# slave-16.net
KiCad netlist of a schematic drawn in EAGLE
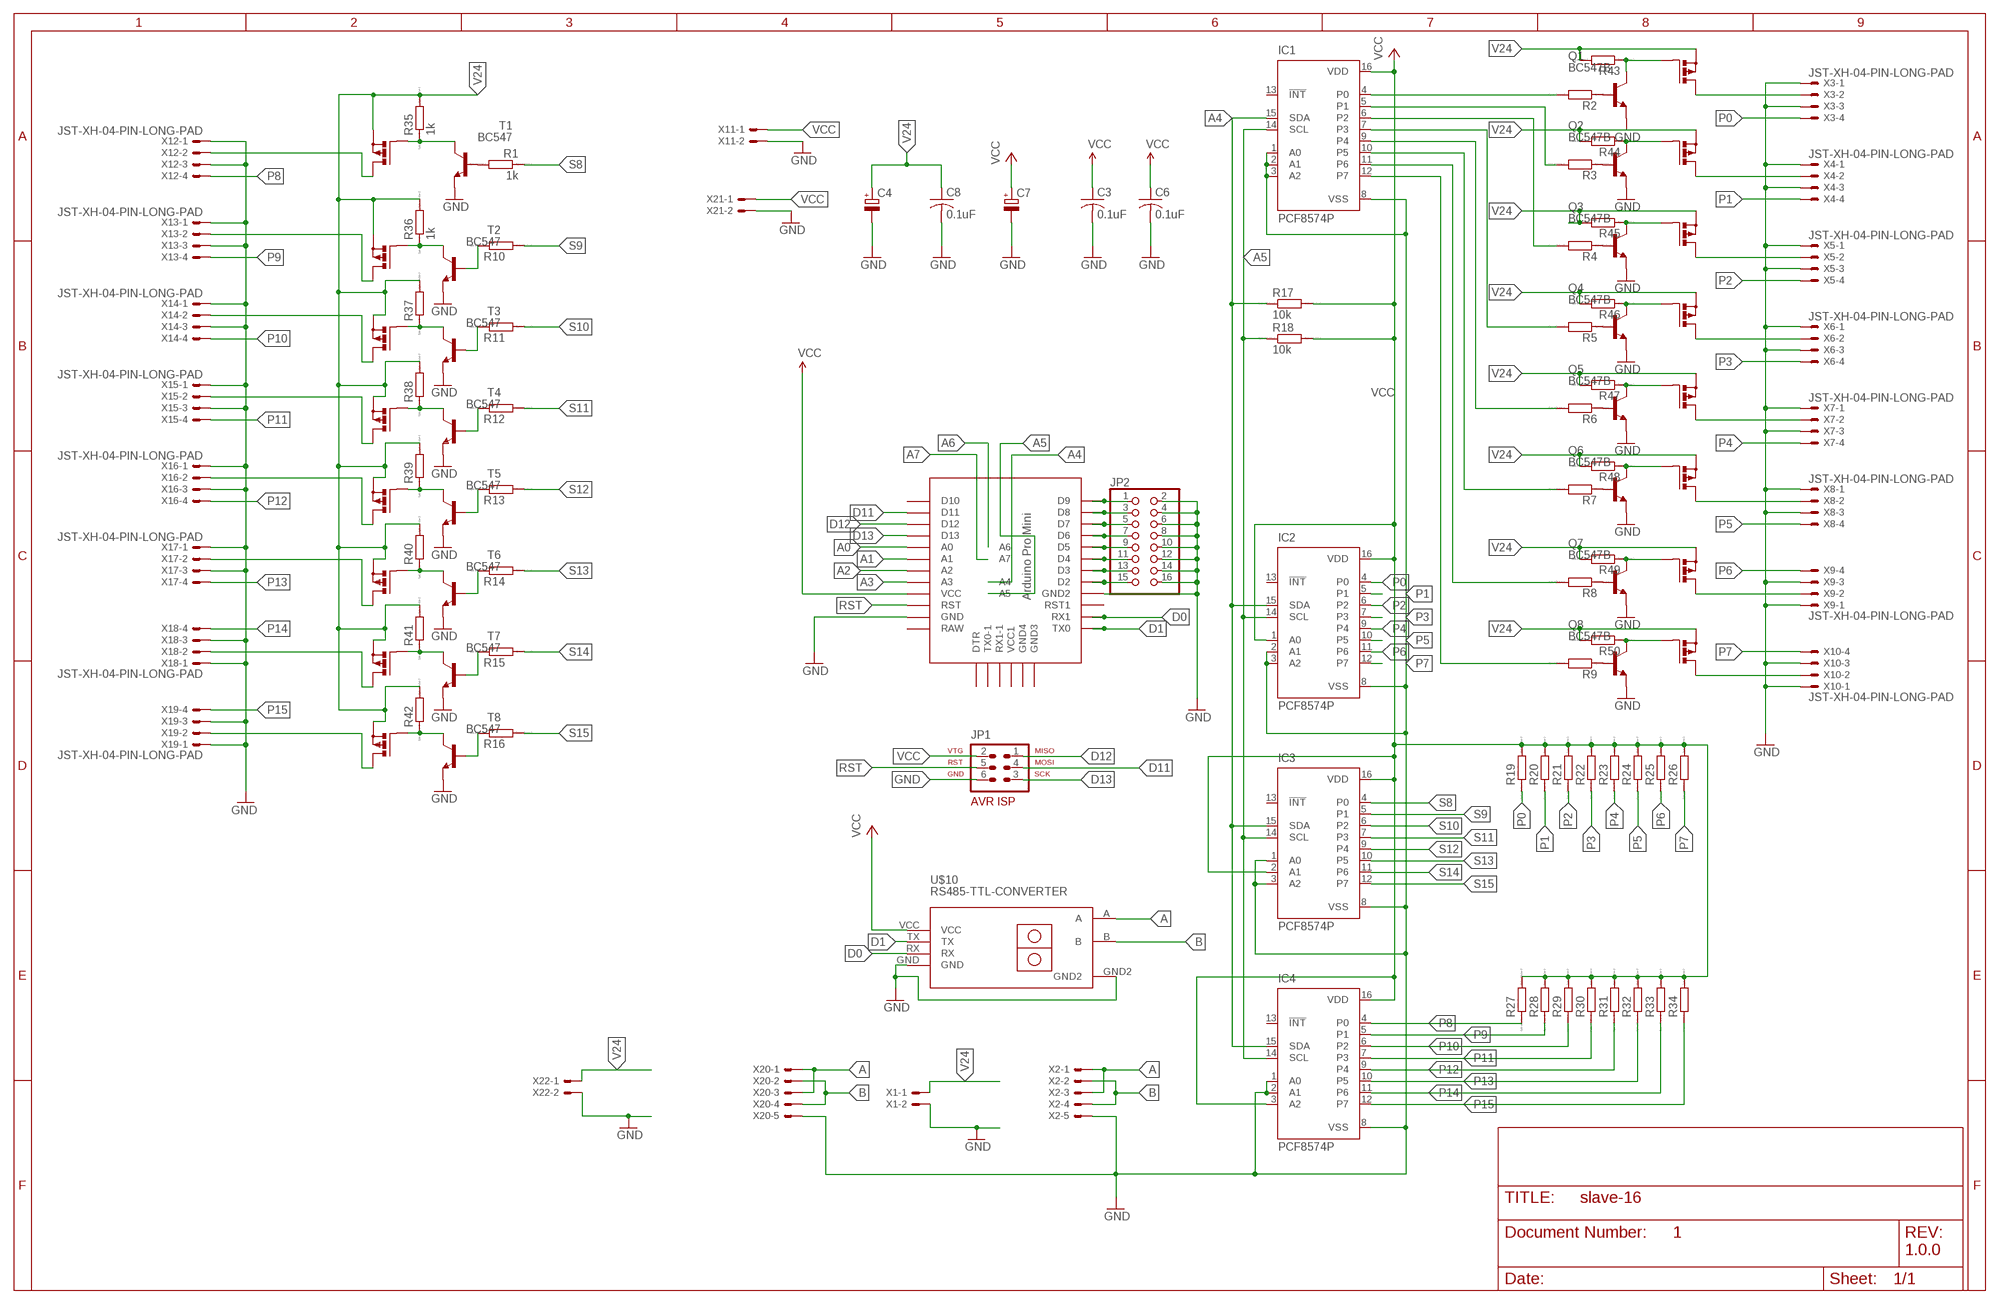
[diagram p0: schematic, sheet 1]

(export (version "E")
  (design (tool "Eeschema 10.0.6"))
  (components
    (comp (ref "C3")
      (value "0.1uF")
      (footprint "eagle-import:C0805")
      (libsource (lib "eagle-import") (part "C-USC0805"))
    )
    (comp (ref "C4")
      (value "CPOL-EUSANYO_SMD_C6")
      (footprint "eagle-import:SANYO-OSCON_SMD_C6")
      (libsource (lib "eagle-import") (part "CPOL-EUSANYO_SMD_C6"))
    )
    (comp (ref "C6")
      (value "0.1uF")
      (footprint "eagle-import:C0805")
      (libsource (lib "eagle-import") (part "C-USC0805"))
    )
    (comp (ref "C7")
      (value "CPOL-EUSANYO_SMD_C6")
      (footprint "eagle-import:SANYO-OSCON_SMD_C6")
      (libsource (lib "eagle-import") (part "CPOL-EUSANYO_SMD_C6"))
    )
    (comp (ref "C8")
      (value "0.1uF")
      (footprint "eagle-import:C0805")
      (libsource (lib "eagle-import") (part "C-USC0805"))
    )
    (comp (ref "IC1")
      (value "PCF8574P")
      (footprint "eagle-import:DIL16")
      (fields (field (name "MPN") "PCF8574PN"))
      (libsource (lib "eagle-import") (part "PCF8574P"))
    )
    (comp (ref "IC2")
      (value "PCF8574P")
      (footprint "eagle-import:DIL16")
      (fields (field (name "MPN") "PCF8574PN"))
      (libsource (lib "eagle-import") (part "PCF8574P"))
    )
    (comp (ref "IC3")
      (value "PCF8574P")
      (footprint "eagle-import:DIL16")
      (fields (field (name "MPN") "PCF8574PN"))
      (libsource (lib "eagle-import") (part "PCF8574P"))
    )
    (comp (ref "IC4")
      (value "PCF8574P")
      (footprint "eagle-import:DIL16")
      (fields (field (name "MPN") "PCF8574PN"))
      (libsource (lib "eagle-import") (part "PCF8574P"))
    )
    (comp (ref "JP1")
      (value "AVR-ISP-6")
      (footprint "eagle-import:AVR-ISP-6")
      (libsource (lib "eagle-import") (part "AVR-ISP-6"))
    )
    (comp (ref "JP2")
      (value "PINHD-2X8")
      (footprint "eagle-import:2X08")
      (libsource (lib "eagle-import") (part "PINHD-2X8"))
    )
    (comp (ref "Q1")
      (value "BC547B")
      (footprint "eagle-import:TO92")
      (libsource (lib "eagle-import") (part "BC547B"))
    )
    (comp (ref "Q2")
      (value "BC547B")
      (footprint "eagle-import:TO92")
      (libsource (lib "eagle-import") (part "BC547B"))
    )
    (comp (ref "Q3")
      (value "BC547B")
      (footprint "eagle-import:TO92")
      (libsource (lib "eagle-import") (part "BC547B"))
    )
    (comp (ref "Q4")
      (value "BC547B")
      (footprint "eagle-import:TO92")
      (libsource (lib "eagle-import") (part "BC547B"))
    )
    (comp (ref "Q5")
      (value "BC547B")
      (footprint "eagle-import:TO92")
      (libsource (lib "eagle-import") (part "BC547B"))
    )
    (comp (ref "Q6")
      (value "BC547B")
      (footprint "eagle-import:TO92")
      (libsource (lib "eagle-import") (part "BC547B"))
    )
    (comp (ref "Q7")
      (value "BC547B")
      (footprint "eagle-import:TO92")
      (libsource (lib "eagle-import") (part "BC547B"))
    )
    (comp (ref "Q8")
      (value "BC547B")
      (footprint "eagle-import:TO92")
      (libsource (lib "eagle-import") (part "BC547B"))
    )
    (comp (ref "R1")
      (value "1k")
      (footprint "eagle-import:R1206")
      (libsource (lib "eagle-import") (part "RR1206"))
    )
    (comp (ref "R2")
      (value "RR1206")
      (footprint "eagle-import:R1206")
      (libsource (lib "eagle-import") (part "RR1206"))
    )
    (comp (ref "R3")
      (value "RR1206")
      (footprint "eagle-import:R1206")
      (libsource (lib "eagle-import") (part "RR1206"))
    )
    (comp (ref "R4")
      (value "RR1206")
      (footprint "eagle-import:R1206")
      (libsource (lib "eagle-import") (part "RR1206"))
    )
    (comp (ref "R5")
      (value "RR1206")
      (footprint "eagle-import:R1206")
      (libsource (lib "eagle-import") (part "RR1206"))
    )
    (comp (ref "R6")
      (value "RR1206")
      (footprint "eagle-import:R1206")
      (libsource (lib "eagle-import") (part "RR1206"))
    )
    (comp (ref "R7")
      (value "RR1206")
      (footprint "eagle-import:R1206")
      (libsource (lib "eagle-import") (part "RR1206"))
    )
    (comp (ref "R8")
      (value "RR1206")
      (footprint "eagle-import:R1206")
      (libsource (lib "eagle-import") (part "RR1206"))
    )
    (comp (ref "R9")
      (value "RR1206")
      (footprint "eagle-import:R1206")
      (libsource (lib "eagle-import") (part "RR1206"))
    )
    (comp (ref "R10")
      (value "RR1206")
      (footprint "eagle-import:R1206")
      (libsource (lib "eagle-import") (part "RR1206"))
    )
    (comp (ref "R11")
      (value "RR1206")
      (footprint "eagle-import:R1206")
      (libsource (lib "eagle-import") (part "RR1206"))
    )
    (comp (ref "R12")
      (value "RR1206")
      (footprint "eagle-import:R1206")
      (libsource (lib "eagle-import") (part "RR1206"))
    )
    (comp (ref "R13")
      (value "RR1206")
      (footprint "eagle-import:R1206")
      (libsource (lib "eagle-import") (part "RR1206"))
    )
    (comp (ref "R14")
      (value "RR1206")
      (footprint "eagle-import:R1206")
      (libsource (lib "eagle-import") (part "RR1206"))
    )
    (comp (ref "R15")
      (value "RR1206")
      (footprint "eagle-import:R1206")
      (libsource (lib "eagle-import") (part "RR1206"))
    )
    (comp (ref "R16")
      (value "RR1206")
      (footprint "eagle-import:R1206")
      (libsource (lib "eagle-import") (part "RR1206"))
    )
    (comp (ref "R17")
      (value "10k")
      (footprint "eagle-import:R1206")
      (libsource (lib "eagle-import") (part "RR1206"))
    )
    (comp (ref "R18")
      (value "10k")
      (footprint "eagle-import:R1206")
      (libsource (lib "eagle-import") (part "RR1206"))
    )
    (comp (ref "R19")
      (value "RR1206")
      (footprint "eagle-import:R1206")
      (libsource (lib "eagle-import") (part "RR1206"))
    )
    (comp (ref "R20")
      (value "RR1206")
      (footprint "eagle-import:R1206")
      (libsource (lib "eagle-import") (part "RR1206"))
    )
    (comp (ref "R21")
      (value "RR1206")
      (footprint "eagle-import:R1206")
      (libsource (lib "eagle-import") (part "RR1206"))
    )
    (comp (ref "R22")
      (value "RR1206")
      (footprint "eagle-import:R1206")
      (libsource (lib "eagle-import") (part "RR1206"))
    )
    (comp (ref "R23")
      (value "RR1206")
      (footprint "eagle-import:R1206")
      (libsource (lib "eagle-import") (part "RR1206"))
    )
    (comp (ref "R24")
      (value "RR1206")
      (footprint "eagle-import:R1206")
      (libsource (lib "eagle-import") (part "RR1206"))
    )
    (comp (ref "R25")
      (value "RR1206")
      (footprint "eagle-import:R1206")
      (libsource (lib "eagle-import") (part "RR1206"))
    )
    (comp (ref "R26")
      (value "RR1206")
      (footprint "eagle-import:R1206")
      (libsource (lib "eagle-import") (part "RR1206"))
    )
    (comp (ref "R27")
      (value "RR1206")
      (footprint "eagle-import:R1206")
      (libsource (lib "eagle-import") (part "RR1206"))
    )
    (comp (ref "R28")
      (value "RR1206")
      (footprint "eagle-import:R1206")
      (libsource (lib "eagle-import") (part "RR1206"))
    )
    (comp (ref "R29")
      (value "RR1206")
      (footprint "eagle-import:R1206")
      (libsource (lib "eagle-import") (part "RR1206"))
    )
    (comp (ref "R30")
      (value "RR1206")
      (footprint "eagle-import:R1206")
      (libsource (lib "eagle-import") (part "RR1206"))
    )
    (comp (ref "R31")
      (value "RR1206")
      (footprint "eagle-import:R1206")
      (libsource (lib "eagle-import") (part "RR1206"))
    )
    (comp (ref "R32")
      (value "RR1206")
      (footprint "eagle-import:R1206")
      (libsource (lib "eagle-import") (part "RR1206"))
    )
    (comp (ref "R33")
      (value "RR1206")
      (footprint "eagle-import:R1206")
      (libsource (lib "eagle-import") (part "RR1206"))
    )
    (comp (ref "R34")
      (value "RR1206")
      (footprint "eagle-import:R1206")
      (libsource (lib "eagle-import") (part "RR1206"))
    )
    (comp (ref "R35")
      (value "1k")
      (footprint "eagle-import:R1206")
      (libsource (lib "eagle-import") (part "RR1206"))
    )
    (comp (ref "R36")
      (value "1k")
      (footprint "eagle-import:R1206")
      (libsource (lib "eagle-import") (part "RR1206"))
    )
    (comp (ref "R37")
      (value "RR1206")
      (footprint "eagle-import:R1206")
      (libsource (lib "eagle-import") (part "RR1206"))
    )
    (comp (ref "R38")
      (value "RR1206")
      (footprint "eagle-import:R1206")
      (libsource (lib "eagle-import") (part "RR1206"))
    )
    (comp (ref "R39")
      (value "RR1206")
      (footprint "eagle-import:R1206")
      (libsource (lib "eagle-import") (part "RR1206"))
    )
    (comp (ref "R40")
      (value "RR1206")
      (footprint "eagle-import:R1206")
      (libsource (lib "eagle-import") (part "RR1206"))
    )
    (comp (ref "R41")
      (value "RR1206")
      (footprint "eagle-import:R1206")
      (libsource (lib "eagle-import") (part "RR1206"))
    )
    (comp (ref "R42")
      (value "RR1206")
      (footprint "eagle-import:R1206")
      (libsource (lib "eagle-import") (part "RR1206"))
    )
    (comp (ref "R43")
      (value "RR1206")
      (footprint "eagle-import:R1206")
      (libsource (lib "eagle-import") (part "RR1206"))
    )
    (comp (ref "R44")
      (value "RR1206")
      (footprint "eagle-import:R1206")
      (libsource (lib "eagle-import") (part "RR1206"))
    )
    (comp (ref "R45")
      (value "RR1206")
      (footprint "eagle-import:R1206")
      (libsource (lib "eagle-import") (part "RR1206"))
    )
    (comp (ref "R46")
      (value "RR1206")
      (footprint "eagle-import:R1206")
      (libsource (lib "eagle-import") (part "RR1206"))
    )
    (comp (ref "R47")
      (value "RR1206")
      (footprint "eagle-import:R1206")
      (libsource (lib "eagle-import") (part "RR1206"))
    )
    (comp (ref "R48")
      (value "RR1206")
      (footprint "eagle-import:R1206")
      (libsource (lib "eagle-import") (part "RR1206"))
    )
    (comp (ref "R49")
      (value "RR1206")
      (footprint "eagle-import:R1206")
      (libsource (lib "eagle-import") (part "RR1206"))
    )
    (comp (ref "R50")
      (value "RR1206")
      (footprint "eagle-import:R1206")
      (libsource (lib "eagle-import") (part "RR1206"))
    )
    (comp (ref "T1")
      (value "BC547")
      (footprint "eagle-import:TO92")
      (libsource (lib "eagle-import") (part "transistor_402_BC547"))
    )
    (comp (ref "T2")
      (value "BC547")
      (footprint "eagle-import:TO92")
      (libsource (lib "eagle-import") (part "transistor_402_BC547"))
    )
    (comp (ref "T3")
      (value "BC547")
      (footprint "eagle-import:TO92")
      (libsource (lib "eagle-import") (part "transistor_402_BC547"))
    )
    (comp (ref "T4")
      (value "BC547")
      (footprint "eagle-import:TO92")
      (libsource (lib "eagle-import") (part "transistor_402_BC547"))
    )
    (comp (ref "T5")
      (value "BC547")
      (footprint "eagle-import:TO92")
      (libsource (lib "eagle-import") (part "transistor_402_BC547"))
    )
    (comp (ref "T6")
      (value "BC547")
      (footprint "eagle-import:TO92")
      (libsource (lib "eagle-import") (part "transistor_402_BC547"))
    )
    (comp (ref "T7")
      (value "BC547")
      (footprint "eagle-import:TO92")
      (libsource (lib "eagle-import") (part "transistor_402_BC547"))
    )
    (comp (ref "T8")
      (value "BC547")
      (footprint "eagle-import:TO92")
      (libsource (lib "eagle-import") (part "transistor_402_BC547"))
    )
    (comp (ref "U$1")
      (value "IRLML6402")
      (footprint "eagle-import:SOT-23")
      (libsource (lib "eagle-import") (part "IRLML6402"))
    )
    (comp (ref "U$2")
      (value "IRLML6402")
      (footprint "eagle-import:SOT-23")
      (libsource (lib "eagle-import") (part "IRLML6402"))
    )
    (comp (ref "U$3")
      (value "IRLML6402")
      (footprint "eagle-import:SOT-23")
      (libsource (lib "eagle-import") (part "IRLML6402"))
    )
    (comp (ref "U$4")
      (value "IRLML6402")
      (footprint "eagle-import:SOT-23")
      (libsource (lib "eagle-import") (part "IRLML6402"))
    )
    (comp (ref "U$5")
      (value "IRLML6402")
      (footprint "eagle-import:SOT-23")
      (libsource (lib "eagle-import") (part "IRLML6402"))
    )
    (comp (ref "U$6")
      (value "IRLML6402")
      (footprint "eagle-import:SOT-23")
      (libsource (lib "eagle-import") (part "IRLML6402"))
    )
    (comp (ref "U$7")
      (value "IRLML6402")
      (footprint "eagle-import:SOT-23")
      (libsource (lib "eagle-import") (part "IRLML6402"))
    )
    (comp (ref "U$8")
      (value "IRLML6402")
      (footprint "eagle-import:SOT-23")
      (libsource (lib "eagle-import") (part "IRLML6402"))
    )
    (comp (ref "U$10")
      (value "RS485-TTL-CONVERTER")
      (footprint "eagle-import:RS485-TTL-CONVERTER")
      (libsource (lib "eagle-import") (part "RS485-TTL-CONVERTER"))
    )
    (comp (ref "U$12")
      (value "IRLML6402")
      (footprint "eagle-import:SOT-23")
      (libsource (lib "eagle-import") (part "IRLML6402"))
    )
    (comp (ref "U$13")
      (value "IRLML6402")
      (footprint "eagle-import:SOT-23")
      (libsource (lib "eagle-import") (part "IRLML6402"))
    )
    (comp (ref "U$14")
      (value "IRLML6402")
      (footprint "eagle-import:SOT-23")
      (libsource (lib "eagle-import") (part "IRLML6402"))
    )
    (comp (ref "U$15")
      (value "IRLML6402")
      (footprint "eagle-import:SOT-23")
      (libsource (lib "eagle-import") (part "IRLML6402"))
    )
    (comp (ref "U$16")
      (value "IRLML6402")
      (footprint "eagle-import:SOT-23")
      (libsource (lib "eagle-import") (part "IRLML6402"))
    )
    (comp (ref "U$17")
      (value "IRLML6402")
      (footprint "eagle-import:SOT-23")
      (libsource (lib "eagle-import") (part "IRLML6402"))
    )
    (comp (ref "U$18")
      (value "IRLML6402")
      (footprint "eagle-import:SOT-23")
      (libsource (lib "eagle-import") (part "IRLML6402"))
    )
    (comp (ref "U$19")
      (value "IRLML6402")
      (footprint "eagle-import:SOT-23")
      (libsource (lib "eagle-import") (part "IRLML6402"))
    )
    (comp (ref "U$20")
      (value "PRO-MINI-2")
      (footprint "eagle-import:PRO-MINI-2")
      (libsource (lib "eagle-import") (part "PRO-MINI-2"))
    )
    (comp (ref "X1")
      (value "JST-XH-02-PIN-LONG-PAD")
      (footprint "eagle-import:JST-XH-02-PACKAGE-LONG-PAD")
      (libsource (lib "eagle-import") (part "JST-XH-02-PIN-LONG-PAD"))
    )
    (comp (ref "X2")
      (value "JST-XH-05-PIN-LONG-PAD")
      (footprint "eagle-import:JST-XH-05-PACKAGE-LONG-PAD")
      (libsource (lib "eagle-import") (part "JST-XH-05-PIN-LONG-PAD"))
    )
    (comp (ref "X3")
      (value "JST-XH-04-PIN-LONG-PAD")
      (footprint "eagle-import:JST-XH-04-PACKAGE-LONG-PAD")
      (libsource (lib "eagle-import") (part "JST-XH-04-PIN-LONG-PAD"))
    )
    (comp (ref "X4")
      (value "JST-XH-04-PIN-LONG-PAD")
      (footprint "eagle-import:JST-XH-04-PACKAGE-LONG-PAD")
      (libsource (lib "eagle-import") (part "JST-XH-04-PIN-LONG-PAD"))
    )
    (comp (ref "X5")
      (value "JST-XH-04-PIN-LONG-PAD")
      (footprint "eagle-import:JST-XH-04-PACKAGE-LONG-PAD")
      (libsource (lib "eagle-import") (part "JST-XH-04-PIN-LONG-PAD"))
    )
    (comp (ref "X6")
      (value "JST-XH-04-PIN-LONG-PAD")
      (footprint "eagle-import:JST-XH-04-PACKAGE-LONG-PAD")
      (libsource (lib "eagle-import") (part "JST-XH-04-PIN-LONG-PAD"))
    )
    (comp (ref "X7")
      (value "JST-XH-04-PIN-LONG-PAD")
      (footprint "eagle-import:JST-XH-04-PACKAGE-LONG-PAD")
      (libsource (lib "eagle-import") (part "JST-XH-04-PIN-LONG-PAD"))
    )
    (comp (ref "X8")
      (value "JST-XH-04-PIN-LONG-PAD")
      (footprint "eagle-import:JST-XH-04-PACKAGE-LONG-PAD")
      (libsource (lib "eagle-import") (part "JST-XH-04-PIN-LONG-PAD"))
    )
    (comp (ref "X9")
      (value "JST-XH-04-PIN-LONG-PAD")
      (footprint "eagle-import:JST-XH-04-PACKAGE-LONG-PAD")
      (libsource (lib "eagle-import") (part "JST-XH-04-PIN-LONG-PAD"))
    )
    (comp (ref "X10")
      (value "JST-XH-04-PIN-LONG-PAD")
      (footprint "eagle-import:JST-XH-04-PACKAGE-LONG-PAD")
      (libsource (lib "eagle-import") (part "JST-XH-04-PIN-LONG-PAD"))
    )
    (comp (ref "X11")
      (value "JST-XH-02-PIN-LONG-PAD")
      (footprint "eagle-import:JST-XH-02-PACKAGE-LONG-PAD")
      (libsource (lib "eagle-import") (part "JST-XH-02-PIN-LONG-PAD"))
    )
    (comp (ref "X12")
      (value "JST-XH-04-PIN-LONG-PAD")
      (footprint "eagle-import:JST-XH-04-PACKAGE-LONG-PAD")
      (libsource (lib "eagle-import") (part "JST-XH-04-PIN-LONG-PAD"))
    )
    (comp (ref "X13")
      (value "JST-XH-04-PIN-LONG-PAD")
      (footprint "eagle-import:JST-XH-04-PACKAGE-LONG-PAD")
      (libsource (lib "eagle-import") (part "JST-XH-04-PIN-LONG-PAD"))
    )
    (comp (ref "X14")
      (value "JST-XH-04-PIN-LONG-PAD")
      (footprint "eagle-import:JST-XH-04-PACKAGE-LONG-PAD")
      (libsource (lib "eagle-import") (part "JST-XH-04-PIN-LONG-PAD"))
    )
    (comp (ref "X15")
      (value "JST-XH-04-PIN-LONG-PAD")
      (footprint "eagle-import:JST-XH-04-PACKAGE-LONG-PAD")
      (libsource (lib "eagle-import") (part "JST-XH-04-PIN-LONG-PAD"))
    )
    (comp (ref "X16")
      (value "JST-XH-04-PIN-LONG-PAD")
      (footprint "eagle-import:JST-XH-04-PACKAGE-LONG-PAD")
      (libsource (lib "eagle-import") (part "JST-XH-04-PIN-LONG-PAD"))
    )
    (comp (ref "X17")
      (value "JST-XH-04-PIN-LONG-PAD")
      (footprint "eagle-import:JST-XH-04-PACKAGE-LONG-PAD")
      (libsource (lib "eagle-import") (part "JST-XH-04-PIN-LONG-PAD"))
    )
    (comp (ref "X18")
      (value "JST-XH-04-PIN-LONG-PAD")
      (footprint "eagle-import:JST-XH-04-PACKAGE-LONG-PAD")
      (libsource (lib "eagle-import") (part "JST-XH-04-PIN-LONG-PAD"))
    )
    (comp (ref "X19")
      (value "JST-XH-04-PIN-LONG-PAD")
      (footprint "eagle-import:JST-XH-04-PACKAGE-LONG-PAD")
      (libsource (lib "eagle-import") (part "JST-XH-04-PIN-LONG-PAD"))
    )
    (comp (ref "X20")
      (value "JST-XH-05-PIN-LONG-PAD")
      (footprint "eagle-import:JST-XH-05-PACKAGE-LONG-PAD")
      (libsource (lib "eagle-import") (part "JST-XH-05-PIN-LONG-PAD"))
    )
    (comp (ref "X21")
      (value "JST-XH-02-PIN-LONG-PAD")
      (footprint "eagle-import:JST-XH-02-PACKAGE-LONG-PAD")
      (libsource (lib "eagle-import") (part "JST-XH-02-PIN-LONG-PAD"))
    )
    (comp (ref "X22")
      (value "JST-XH-02-PIN-LONG-PAD")
      (footprint "eagle-import:JST-XH-02-PACKAGE-LONG-PAD")
      (libsource (lib "eagle-import") (part "JST-XH-02-PIN-LONG-PAD"))
    )
  )
  (nets
    (net (code "1") (name "A") (class "Default")
      (node (ref "U$10") (pin "A") (pinfunction "A_A") (pintype "passive"))
      (node (ref "X2") (pin "1") (pinfunction "S_1") (pintype "passive"))
      (node (ref "X2") (pin "3") (pinfunction "S_3") (pintype "passive"))
      (node (ref "X20") (pin "1") (pinfunction "S_1") (pintype "passive"))
      (node (ref "X20") (pin "3") (pinfunction "S_3") (pintype "passive"))
    )
    (net (code "2") (name "A0") (class "Default")
      (node (ref "U$20") (pin "A0") (pinfunction "A0_A0") (pintype "bidirectional"))
    )
    (net (code "3") (name "A1") (class "Default")
      (node (ref "U$20") (pin "A1") (pinfunction "A1_A1") (pintype "bidirectional"))
    )
    (net (code "4") (name "A2") (class "Default")
      (node (ref "U$20") (pin "A2") (pinfunction "A2_A2") (pintype "bidirectional"))
    )
    (net (code "5") (name "A3") (class "Default")
      (node (ref "U$20") (pin "A3") (pinfunction "A3_A3") (pintype "bidirectional"))
    )
    (net (code "6") (name "A4") (class "Default")
      (node (ref "IC1") (pin "15") (pinfunction "SDA_15") (pintype "bidirectional"))
      (node (ref "IC2") (pin "15") (pinfunction "SDA_15") (pintype "bidirectional"))
      (node (ref "IC3") (pin "15") (pinfunction "SDA_15") (pintype "bidirectional"))
      (node (ref "IC4") (pin "15") (pinfunction "SDA_15") (pintype "bidirectional"))
      (node (ref "R17") (pin "1") (pinfunction "1_1") (pintype "passive"))
      (node (ref "U$20") (pin "A4") (pinfunction "A4_A4") (pintype "bidirectional"))
    )
    (net (code "7") (name "A5") (class "Default")
      (node (ref "IC1") (pin "14") (pinfunction "SCL_14") (pintype "input"))
      (node (ref "IC2") (pin "14") (pinfunction "SCL_14") (pintype "input"))
      (node (ref "IC3") (pin "14") (pinfunction "SCL_14") (pintype "input"))
      (node (ref "IC4") (pin "14") (pinfunction "SCL_14") (pintype "input"))
      (node (ref "R18") (pin "1") (pinfunction "1_1") (pintype "passive"))
      (node (ref "U$20") (pin "A5") (pinfunction "A5_A5") (pintype "bidirectional"))
    )
    (net (code "8") (name "A6") (class "Default")
      (node (ref "U$20") (pin "A6") (pinfunction "A6_A6") (pintype "bidirectional"))
    )
    (net (code "9") (name "A7") (class "Default")
      (node (ref "U$20") (pin "A7") (pinfunction "A7_A7") (pintype "bidirectional"))
    )
    (net (code "10") (name "B") (class "Default")
      (node (ref "U$10") (pin "B") (pinfunction "B_B") (pintype "passive"))
      (node (ref "X2") (pin "2") (pinfunction "S_2") (pintype "passive"))
      (node (ref "X2") (pin "4") (pinfunction "S_4") (pintype "passive"))
      (node (ref "X20") (pin "2") (pinfunction "S_2") (pintype "passive"))
      (node (ref "X20") (pin "4") (pinfunction "S_4") (pintype "passive"))
    )
    (net (code "11") (name "D0") (class "Default")
      (node (ref "U$10") (pin "RX") (pinfunction "RX_RX") (pintype "passive"))
      (node (ref "U$20") (pin "RX1") (pinfunction "RX1_RX1") (pintype "bidirectional"))
    )
    (net (code "12") (name "D1") (class "Default")
      (node (ref "U$10") (pin "TX") (pinfunction "TX_TX") (pintype "passive"))
      (node (ref "U$20") (pin "TX0") (pinfunction "TX0_TX0") (pintype "bidirectional"))
    )
    (net (code "13") (name "D11") (class "Default")
      (node (ref "JP1") (pin "4") (pinfunction "4_4") (pintype "passive"))
      (node (ref "U$20") (pin "D11") (pinfunction "D11_D11") (pintype "bidirectional"))
    )
    (net (code "14") (name "D12") (class "Default")
      (node (ref "JP1") (pin "1") (pinfunction "1_1") (pintype "passive"))
      (node (ref "U$20") (pin "D12") (pinfunction "D12_D12") (pintype "bidirectional"))
    )
    (net (code "15") (name "D13") (class "Default")
      (node (ref "JP1") (pin "3") (pinfunction "3_3") (pintype "passive"))
      (node (ref "U$20") (pin "D13") (pinfunction "D13_D13") (pintype "bidirectional"))
    )
    (net (code "16") (name "GND") (class "Default")
      (node (ref "C3") (pin "2") (pinfunction "2_2") (pintype "passive"))
      (node (ref "C4") (pin "-") (pinfunction "-_-") (pintype "passive"))
      (node (ref "C6") (pin "2") (pinfunction "2_2") (pintype "passive"))
      (node (ref "C7") (pin "-") (pinfunction "-_-") (pintype "passive"))
      (node (ref "C8") (pin "2") (pinfunction "2_2") (pintype "passive"))
      (node (ref "IC1") (pin "1") (pinfunction "A0_1") (pintype "input"))
      (node (ref "IC1") (pin "2") (pinfunction "A1_2") (pintype "input"))
      (node (ref "IC1") (pin "3") (pinfunction "A2_3") (pintype "input"))
      (node (ref "IC1") (pin "8") (pinfunction "VSS_8") (pintype "power_in"))
      (node (ref "IC2") (pin "2") (pinfunction "A1_2") (pintype "input"))
      (node (ref "IC2") (pin "3") (pinfunction "A2_3") (pintype "input"))
      (node (ref "IC2") (pin "8") (pinfunction "VSS_8") (pintype "power_in"))
      (node (ref "IC3") (pin "1") (pinfunction "A0_1") (pintype "input"))
      (node (ref "IC3") (pin "3") (pinfunction "A2_3") (pintype "input"))
      (node (ref "IC3") (pin "8") (pinfunction "VSS_8") (pintype "power_in"))
      (node (ref "IC4") (pin "1") (pinfunction "A0_1") (pintype "input"))
      (node (ref "IC4") (pin "2") (pinfunction "A1_2") (pintype "input"))
      (node (ref "IC4") (pin "8") (pinfunction "VSS_8") (pintype "power_in"))
      (node (ref "JP1") (pin "6") (pinfunction "6_6") (pintype "passive"))
      (node (ref "JP2") (pin "10") (pinfunction "10_10") (pintype "passive"))
      (node (ref "JP2") (pin "12") (pinfunction "12_12") (pintype "passive"))
      (node (ref "JP2") (pin "14") (pinfunction "14_14") (pintype "passive"))
      (node (ref "JP2") (pin "16") (pinfunction "16_16") (pintype "passive"))
      (node (ref "JP2") (pin "2") (pinfunction "2_2") (pintype "passive"))
      (node (ref "JP2") (pin "4") (pinfunction "4_4") (pintype "passive"))
      (node (ref "JP2") (pin "6") (pinfunction "6_6") (pintype "passive"))
      (node (ref "JP2") (pin "8") (pinfunction "8_8") (pintype "passive"))
      (node (ref "Q1") (pin "1") (pinfunction "E_1") (pintype "passive"))
      (node (ref "Q2") (pin "1") (pinfunction "E_1") (pintype "passive"))
      (node (ref "Q3") (pin "1") (pinfunction "E_1") (pintype "passive"))
      (node (ref "Q4") (pin "1") (pinfunction "E_1") (pintype "passive"))
      (node (ref "Q5") (pin "1") (pinfunction "E_1") (pintype "passive"))
      (node (ref "Q6") (pin "1") (pinfunction "E_1") (pintype "passive"))
      (node (ref "Q7") (pin "1") (pinfunction "E_1") (pintype "passive"))
      (node (ref "Q8") (pin "1") (pinfunction "E_1") (pintype "passive"))
      (node (ref "T1") (pin "1") (pinfunction "E_1") (pintype "passive"))
      (node (ref "T2") (pin "1") (pinfunction "E_1") (pintype "passive"))
      (node (ref "T3") (pin "1") (pinfunction "E_1") (pintype "passive"))
      (node (ref "T4") (pin "1") (pinfunction "E_1") (pintype "passive"))
      (node (ref "T5") (pin "1") (pinfunction "E_1") (pintype "passive"))
      (node (ref "T6") (pin "1") (pinfunction "E_1") (pintype "passive"))
      (node (ref "T7") (pin "1") (pinfunction "E_1") (pintype "passive"))
      (node (ref "T8") (pin "1") (pinfunction "E_1") (pintype "passive"))
      (node (ref "U$10") (pin "GND") (pinfunction "GND_GND") (pintype "passive"))
      (node (ref "U$10") (pin "GND2") (pinfunction "GND2_GND2") (pintype "power_in"))
      (node (ref "U$20") (pin "GND") (pinfunction "GND_GND") (pintype "bidirectional"))
      (node (ref "U$20") (pin "GND1") (pinfunction "GND2_GND1") (pintype "bidirectional"))
      (node (ref "X1") (pin "2") (pinfunction "S_2") (pintype "passive"))
      (node (ref "X10") (pin "1") (pinfunction "S_1") (pintype "passive"))
      (node (ref "X10") (pin "3") (pinfunction "S_3") (pintype "passive"))
      (node (ref "X11") (pin "2") (pinfunction "S_2") (pintype "passive"))
      (node (ref "X12") (pin "1") (pinfunction "S_1") (pintype "passive"))
      (node (ref "X12") (pin "3") (pinfunction "S_3") (pintype "passive"))
      (node (ref "X13") (pin "1") (pinfunction "S_1") (pintype "passive"))
      (node (ref "X13") (pin "3") (pinfunction "S_3") (pintype "passive"))
      (node (ref "X14") (pin "1") (pinfunction "S_1") (pintype "passive"))
      (node (ref "X14") (pin "3") (pinfunction "S_3") (pintype "passive"))
      (node (ref "X15") (pin "1") (pinfunction "S_1") (pintype "passive"))
      (node (ref "X15") (pin "3") (pinfunction "S_3") (pintype "passive"))
      (node (ref "X16") (pin "1") (pinfunction "S_1") (pintype "passive"))
      (node (ref "X16") (pin "3") (pinfunction "S_3") (pintype "passive"))
      (node (ref "X17") (pin "1") (pinfunction "S_1") (pintype "passive"))
      (node (ref "X17") (pin "3") (pinfunction "S_3") (pintype "passive"))
      (node (ref "X18") (pin "1") (pinfunction "S_1") (pintype "passive"))
      (node (ref "X18") (pin "3") (pinfunction "S_3") (pintype "passive"))
      (node (ref "X19") (pin "1") (pinfunction "S_1") (pintype "passive"))
      (node (ref "X19") (pin "3") (pinfunction "S_3") (pintype "passive"))
      (node (ref "X2") (pin "5") (pinfunction "S_5") (pintype "passive"))
      (node (ref "X20") (pin "5") (pinfunction "S_5") (pintype "passive"))
      (node (ref "X21") (pin "2") (pinfunction "S_2") (pintype "passive"))
      (node (ref "X22") (pin "2") (pinfunction "S_2") (pintype "passive"))
      (node (ref "X3") (pin "1") (pinfunction "S_1") (pintype "passive"))
      (node (ref "X3") (pin "3") (pinfunction "S_3") (pintype "passive"))
      (node (ref "X4") (pin "1") (pinfunction "S_1") (pintype "passive"))
      (node (ref "X4") (pin "3") (pinfunction "S_3") (pintype "passive"))
      (node (ref "X5") (pin "1") (pinfunction "S_1") (pintype "passive"))
      (node (ref "X5") (pin "3") (pinfunction "S_3") (pintype "passive"))
      (node (ref "X6") (pin "1") (pinfunction "S_1") (pintype "passive"))
      (node (ref "X6") (pin "3") (pinfunction "S_3") (pintype "passive"))
      (node (ref "X7") (pin "1") (pinfunction "S_1") (pintype "passive"))
      (node (ref "X7") (pin "3") (pinfunction "S_3") (pintype "passive"))
      (node (ref "X8") (pin "1") (pinfunction "S_1") (pintype "passive"))
      (node (ref "X8") (pin "3") (pinfunction "S_3") (pintype "passive"))
      (node (ref "X9") (pin "1") (pinfunction "S_1") (pintype "passive"))
      (node (ref "X9") (pin "3") (pinfunction "S_3") (pintype "passive"))
    )
    (net (code "17") (name "Net-(IC1-P0)") (class "Default")
      (node (ref "IC1") (pin "4") (pinfunction "P0_4") (pintype "bidirectional"))
      (node (ref "R2") (pin "2") (pinfunction "2_2") (pintype "passive"))
    )
    (net (code "18") (name "Net-(IC1-P1)") (class "Default")
      (node (ref "IC1") (pin "5") (pinfunction "P1_5") (pintype "bidirectional"))
      (node (ref "R3") (pin "2") (pinfunction "2_2") (pintype "passive"))
    )
    (net (code "19") (name "Net-(IC1-P2)") (class "Default")
      (node (ref "IC1") (pin "6") (pinfunction "P2_6") (pintype "bidirectional"))
      (node (ref "R4") (pin "2") (pinfunction "2_2") (pintype "passive"))
    )
    (net (code "20") (name "Net-(IC1-P3)") (class "Default")
      (node (ref "IC1") (pin "7") (pinfunction "P3_7") (pintype "bidirectional"))
      (node (ref "R5") (pin "2") (pinfunction "2_2") (pintype "passive"))
    )
    (net (code "21") (name "Net-(IC1-P4)") (class "Default")
      (node (ref "IC1") (pin "9") (pinfunction "P4_9") (pintype "bidirectional"))
      (node (ref "R6") (pin "2") (pinfunction "2_2") (pintype "passive"))
    )
    (net (code "22") (name "Net-(IC1-P5)") (class "Default")
      (node (ref "IC1") (pin "10") (pinfunction "P5_10") (pintype "bidirectional"))
      (node (ref "R7") (pin "2") (pinfunction "2_2") (pintype "passive"))
    )
    (net (code "23") (name "Net-(IC1-P6)") (class "Default")
      (node (ref "IC1") (pin "11") (pinfunction "P6_11") (pintype "bidirectional"))
      (node (ref "R8") (pin "2") (pinfunction "2_2") (pintype "passive"))
    )
    (net (code "24") (name "Net-(IC1-P7)") (class "Default")
      (node (ref "IC1") (pin "12") (pinfunction "P7_12") (pintype "bidirectional"))
      (node (ref "R9") (pin "2") (pinfunction "2_2") (pintype "passive"))
    )
    (net (code "25") (name "Net-(JP2-Pad1)") (class "Default")
      (node (ref "JP2") (pin "1") (pinfunction "1_1") (pintype "passive"))
      (node (ref "U$20") (pin "D9") (pinfunction "D9_D9") (pintype "bidirectional"))
    )
    (net (code "26") (name "Net-(JP2-Pad3)") (class "Default")
      (node (ref "JP2") (pin "3") (pinfunction "3_3") (pintype "passive"))
      (node (ref "U$20") (pin "D8") (pinfunction "D8_D8") (pintype "bidirectional"))
    )
    (net (code "27") (name "Net-(JP2-Pad5)") (class "Default")
      (node (ref "JP2") (pin "5") (pinfunction "5_5") (pintype "passive"))
      (node (ref "U$20") (pin "D7") (pinfunction "D7_D7") (pintype "bidirectional"))
    )
    (net (code "28") (name "Net-(JP2-Pad7)") (class "Default")
      (node (ref "JP2") (pin "7") (pinfunction "7_7") (pintype "passive"))
      (node (ref "U$20") (pin "D6") (pinfunction "D6_D6") (pintype "bidirectional"))
    )
    (net (code "29") (name "Net-(JP2-Pad9)") (class "Default")
      (node (ref "JP2") (pin "9") (pinfunction "9_9") (pintype "passive"))
      (node (ref "U$20") (pin "D5") (pinfunction "D5_D5") (pintype "bidirectional"))
    )
    (net (code "30") (name "Net-(JP2-Pad11)") (class "Default")
      (node (ref "JP2") (pin "11") (pinfunction "11_11") (pintype "passive"))
      (node (ref "U$20") (pin "D4") (pinfunction "D4_D4") (pintype "bidirectional"))
    )
    (net (code "31") (name "Net-(JP2-Pad13)") (class "Default")
      (node (ref "JP2") (pin "13") (pinfunction "13_13") (pintype "passive"))
      (node (ref "U$20") (pin "D3") (pinfunction "D3_D3") (pintype "bidirectional"))
    )
    (net (code "32") (name "Net-(JP2-Pad15)") (class "Default")
      (node (ref "JP2") (pin "15") (pinfunction "15_15") (pintype "passive"))
      (node (ref "U$20") (pin "D2") (pinfunction "D2_D2") (pintype "bidirectional"))
    )
    (net (code "33") (name "Net-(Q1-B)") (class "Default")
      (node (ref "Q1") (pin "2") (pinfunction "B_2") (pintype "passive"))
      (node (ref "R2") (pin "1") (pinfunction "1_1") (pintype "passive"))
    )
    (net (code "34") (name "Net-(Q1-C)") (class "Default")
      (node (ref "Q1") (pin "3") (pinfunction "C_3") (pintype "passive"))
      (node (ref "R43") (pin "1") (pinfunction "1_1") (pintype "passive"))
      (node (ref "U$1") (pin "P1") (pinfunction "G_P1") (pintype "passive"))
    )
    (net (code "35") (name "Net-(Q2-B)") (class "Default")
      (node (ref "Q2") (pin "2") (pinfunction "B_2") (pintype "passive"))
      (node (ref "R3") (pin "1") (pinfunction "1_1") (pintype "passive"))
    )
    (net (code "36") (name "Net-(Q2-C)") (class "Default")
      (node (ref "Q2") (pin "3") (pinfunction "C_3") (pintype "passive"))
      (node (ref "R44") (pin "1") (pinfunction "1_1") (pintype "passive"))
      (node (ref "U$2") (pin "P1") (pinfunction "G_P1") (pintype "passive"))
    )
    (net (code "37") (name "Net-(Q3-B)") (class "Default")
      (node (ref "Q3") (pin "2") (pinfunction "B_2") (pintype "passive"))
      (node (ref "R4") (pin "1") (pinfunction "1_1") (pintype "passive"))
    )
    (net (code "38") (name "Net-(Q3-C)") (class "Default")
      (node (ref "Q3") (pin "3") (pinfunction "C_3") (pintype "passive"))
      (node (ref "R45") (pin "1") (pinfunction "1_1") (pintype "passive"))
      (node (ref "U$3") (pin "P1") (pinfunction "G_P1") (pintype "passive"))
    )
    (net (code "39") (name "Net-(Q4-B)") (class "Default")
      (node (ref "Q4") (pin "2") (pinfunction "B_2") (pintype "passive"))
      (node (ref "R5") (pin "1") (pinfunction "1_1") (pintype "passive"))
    )
    (net (code "40") (name "Net-(Q4-C)") (class "Default")
      (node (ref "Q4") (pin "3") (pinfunction "C_3") (pintype "passive"))
      (node (ref "R46") (pin "1") (pinfunction "1_1") (pintype "passive"))
      (node (ref "U$4") (pin "P1") (pinfunction "G_P1") (pintype "passive"))
    )
    (net (code "41") (name "Net-(Q5-B)") (class "Default")
      (node (ref "Q5") (pin "2") (pinfunction "B_2") (pintype "passive"))
      (node (ref "R6") (pin "1") (pinfunction "1_1") (pintype "passive"))
    )
    (net (code "42") (name "Net-(Q5-C)") (class "Default")
      (node (ref "Q5") (pin "3") (pinfunction "C_3") (pintype "passive"))
      (node (ref "R47") (pin "1") (pinfunction "1_1") (pintype "passive"))
      (node (ref "U$5") (pin "P1") (pinfunction "G_P1") (pintype "passive"))
    )
    (net (code "43") (name "Net-(Q6-B)") (class "Default")
      (node (ref "Q6") (pin "2") (pinfunction "B_2") (pintype "passive"))
      (node (ref "R7") (pin "1") (pinfunction "1_1") (pintype "passive"))
    )
    (net (code "44") (name "Net-(Q6-C)") (class "Default")
      (node (ref "Q6") (pin "3") (pinfunction "C_3") (pintype "passive"))
      (node (ref "R48") (pin "1") (pinfunction "1_1") (pintype "passive"))
      (node (ref "U$6") (pin "P1") (pinfunction "G_P1") (pintype "passive"))
    )
    (net (code "45") (name "Net-(Q7-B)") (class "Default")
      (node (ref "Q7") (pin "2") (pinfunction "B_2") (pintype "passive"))
      (node (ref "R8") (pin "1") (pinfunction "1_1") (pintype "passive"))
    )
    (net (code "46") (name "Net-(Q7-C)") (class "Default")
      (node (ref "Q7") (pin "3") (pinfunction "C_3") (pintype "passive"))
      (node (ref "R49") (pin "1") (pinfunction "1_1") (pintype "passive"))
      (node (ref "U$7") (pin "P1") (pinfunction "G_P1") (pintype "passive"))
    )
    (net (code "47") (name "Net-(Q8-B)") (class "Default")
      (node (ref "Q8") (pin "2") (pinfunction "B_2") (pintype "passive"))
      (node (ref "R9") (pin "1") (pinfunction "1_1") (pintype "passive"))
    )
    (net (code "48") (name "Net-(Q8-C)") (class "Default")
      (node (ref "Q8") (pin "3") (pinfunction "C_3") (pintype "passive"))
      (node (ref "R50") (pin "1") (pinfunction "1_1") (pintype "passive"))
      (node (ref "U$8") (pin "P1") (pinfunction "G_P1") (pintype "passive"))
    )
    (net (code "49") (name "Net-(T1-B)") (class "Default")
      (node (ref "R1") (pin "2") (pinfunction "2_2") (pintype "passive"))
      (node (ref "T1") (pin "2") (pinfunction "B_2") (pintype "passive"))
    )
    (net (code "50") (name "Net-(T1-C)") (class "Default")
      (node (ref "R35") (pin "1") (pinfunction "1_1") (pintype "passive"))
      (node (ref "T1") (pin "3") (pinfunction "C_3") (pintype "passive"))
      (node (ref "U$12") (pin "P1") (pinfunction "G_P1") (pintype "passive"))
    )
    (net (code "51") (name "Net-(T2-B)") (class "Default")
      (node (ref "R10") (pin "1") (pinfunction "1_1") (pintype "passive"))
      (node (ref "T2") (pin "2") (pinfunction "B_2") (pintype "passive"))
    )
    (net (code "52") (name "Net-(T2-C)") (class "Default")
      (node (ref "R36") (pin "1") (pinfunction "1_1") (pintype "passive"))
      (node (ref "T2") (pin "3") (pinfunction "C_3") (pintype "passive"))
      (node (ref "U$13") (pin "P1") (pinfunction "G_P1") (pintype "passive"))
    )
    (net (code "53") (name "Net-(T3-B)") (class "Default")
      (node (ref "R11") (pin "1") (pinfunction "1_1") (pintype "passive"))
      (node (ref "T3") (pin "2") (pinfunction "B_2") (pintype "passive"))
    )
    (net (code "54") (name "Net-(T3-C)") (class "Default")
      (node (ref "R37") (pin "1") (pinfunction "1_1") (pintype "passive"))
      (node (ref "T3") (pin "3") (pinfunction "C_3") (pintype "passive"))
      (node (ref "U$14") (pin "P1") (pinfunction "G_P1") (pintype "passive"))
    )
    (net (code "55") (name "Net-(T4-B)") (class "Default")
      (node (ref "R12") (pin "1") (pinfunction "1_1") (pintype "passive"))
      (node (ref "T4") (pin "2") (pinfunction "B_2") (pintype "passive"))
    )
    (net (code "56") (name "Net-(T4-C)") (class "Default")
      (node (ref "R38") (pin "1") (pinfunction "1_1") (pintype "passive"))
      (node (ref "T4") (pin "3") (pinfunction "C_3") (pintype "passive"))
      (node (ref "U$15") (pin "P1") (pinfunction "G_P1") (pintype "passive"))
    )
    (net (code "57") (name "Net-(T5-B)") (class "Default")
      (node (ref "R13") (pin "1") (pinfunction "1_1") (pintype "passive"))
      (node (ref "T5") (pin "2") (pinfunction "B_2") (pintype "passive"))
    )
    (net (code "58") (name "Net-(T5-C)") (class "Default")
      (node (ref "R39") (pin "1") (pinfunction "1_1") (pintype "passive"))
      (node (ref "T5") (pin "3") (pinfunction "C_3") (pintype "passive"))
      (node (ref "U$16") (pin "P1") (pinfunction "G_P1") (pintype "passive"))
    )
    (net (code "59") (name "Net-(T6-B)") (class "Default")
      (node (ref "R14") (pin "1") (pinfunction "1_1") (pintype "passive"))
      (node (ref "T6") (pin "2") (pinfunction "B_2") (pintype "passive"))
    )
    (net (code "60") (name "Net-(T6-C)") (class "Default")
      (node (ref "R40") (pin "1") (pinfunction "1_1") (pintype "passive"))
      (node (ref "T6") (pin "3") (pinfunction "C_3") (pintype "passive"))
      (node (ref "U$17") (pin "P1") (pinfunction "G_P1") (pintype "passive"))
    )
    (net (code "61") (name "Net-(T7-B)") (class "Default")
      (node (ref "R15") (pin "1") (pinfunction "1_1") (pintype "passive"))
      (node (ref "T7") (pin "2") (pinfunction "B_2") (pintype "passive"))
    )
    (net (code "62") (name "Net-(T7-C)") (class "Default")
      (node (ref "R41") (pin "1") (pinfunction "1_1") (pintype "passive"))
      (node (ref "T7") (pin "3") (pinfunction "C_3") (pintype "passive"))
      (node (ref "U$18") (pin "P1") (pinfunction "G_P1") (pintype "passive"))
    )
    (net (code "63") (name "Net-(T8-B)") (class "Default")
      (node (ref "R16") (pin "1") (pinfunction "1_1") (pintype "passive"))
      (node (ref "T8") (pin "2") (pinfunction "B_2") (pintype "passive"))
    )
    (net (code "64") (name "Net-(T8-C)") (class "Default")
      (node (ref "R42") (pin "1") (pinfunction "1_1") (pintype "passive"))
      (node (ref "T8") (pin "3") (pinfunction "C_3") (pintype "passive"))
      (node (ref "U$19") (pin "P1") (pinfunction "G_P1") (pintype "passive"))
    )
    (net (code "65") (name "Net-(U$1-D)") (class "Default")
      (node (ref "U$1") (pin "P3") (pinfunction "D_P3") (pintype "passive"))
      (node (ref "X3") (pin "2") (pinfunction "S_2") (pintype "passive"))
    )
    (net (code "66") (name "Net-(U$2-D)") (class "Default")
      (node (ref "U$2") (pin "P3") (pinfunction "D_P3") (pintype "passive"))
      (node (ref "X4") (pin "2") (pinfunction "S_2") (pintype "passive"))
    )
    (net (code "67") (name "Net-(U$3-D)") (class "Default")
      (node (ref "U$3") (pin "P3") (pinfunction "D_P3") (pintype "passive"))
      (node (ref "X5") (pin "2") (pinfunction "S_2") (pintype "passive"))
    )
    (net (code "68") (name "Net-(U$4-D)") (class "Default")
      (node (ref "U$4") (pin "P3") (pinfunction "D_P3") (pintype "passive"))
      (node (ref "X6") (pin "2") (pinfunction "S_2") (pintype "passive"))
    )
    (net (code "69") (name "Net-(U$5-D)") (class "Default")
      (node (ref "U$5") (pin "P3") (pinfunction "D_P3") (pintype "passive"))
      (node (ref "X7") (pin "2") (pinfunction "S_2") (pintype "passive"))
    )
    (net (code "70") (name "Net-(U$6-D)") (class "Default")
      (node (ref "U$6") (pin "P3") (pinfunction "D_P3") (pintype "passive"))
      (node (ref "X8") (pin "2") (pinfunction "S_2") (pintype "passive"))
    )
    (net (code "71") (name "Net-(U$7-D)") (class "Default")
      (node (ref "U$7") (pin "P3") (pinfunction "D_P3") (pintype "passive"))
      (node (ref "X9") (pin "2") (pinfunction "S_2") (pintype "passive"))
    )
    (net (code "72") (name "Net-(U$8-D)") (class "Default")
      (node (ref "U$8") (pin "P3") (pinfunction "D_P3") (pintype "passive"))
      (node (ref "X10") (pin "2") (pinfunction "S_2") (pintype "passive"))
    )
    (net (code "73") (name "Net-(U$12-D)") (class "Default")
      (node (ref "U$12") (pin "P3") (pinfunction "D_P3") (pintype "passive"))
      (node (ref "X12") (pin "2") (pinfunction "S_2") (pintype "passive"))
    )
    (net (code "74") (name "Net-(U$13-D)") (class "Default")
      (node (ref "U$13") (pin "P3") (pinfunction "D_P3") (pintype "passive"))
      (node (ref "X13") (pin "2") (pinfunction "S_2") (pintype "passive"))
    )
    (net (code "75") (name "Net-(U$14-D)") (class "Default")
      (node (ref "U$14") (pin "P3") (pinfunction "D_P3") (pintype "passive"))
      (node (ref "X14") (pin "2") (pinfunction "S_2") (pintype "passive"))
    )
    (net (code "76") (name "Net-(U$15-D)") (class "Default")
      (node (ref "U$15") (pin "P3") (pinfunction "D_P3") (pintype "passive"))
      (node (ref "X15") (pin "2") (pinfunction "S_2") (pintype "passive"))
    )
    (net (code "77") (name "Net-(U$16-D)") (class "Default")
      (node (ref "U$16") (pin "P3") (pinfunction "D_P3") (pintype "passive"))
      (node (ref "X16") (pin "2") (pinfunction "S_2") (pintype "passive"))
    )
    (net (code "78") (name "Net-(U$17-D)") (class "Default")
      (node (ref "U$17") (pin "P3") (pinfunction "D_P3") (pintype "passive"))
      (node (ref "X17") (pin "2") (pinfunction "S_2") (pintype "passive"))
    )
    (net (code "79") (name "Net-(U$18-D)") (class "Default")
      (node (ref "U$18") (pin "P3") (pinfunction "D_P3") (pintype "passive"))
      (node (ref "X18") (pin "2") (pinfunction "S_2") (pintype "passive"))
    )
    (net (code "80") (name "Net-(U$19-D)") (class "Default")
      (node (ref "U$19") (pin "P3") (pinfunction "D_P3") (pintype "passive"))
      (node (ref "X19") (pin "2") (pinfunction "S_2") (pintype "passive"))
    )
    (net (code "81") (name "P0") (class "Default")
      (node (ref "IC2") (pin "4") (pinfunction "P0_4") (pintype "bidirectional"))
      (node (ref "R19") (pin "1") (pinfunction "1_1") (pintype "passive"))
      (node (ref "X3") (pin "4") (pinfunction "S_4") (pintype "passive"))
    )
    (net (code "82") (name "P1") (class "Default")
      (node (ref "IC2") (pin "5") (pinfunction "P1_5") (pintype "bidirectional"))
      (node (ref "R20") (pin "1") (pinfunction "1_1") (pintype "passive"))
      (node (ref "X4") (pin "4") (pinfunction "S_4") (pintype "passive"))
    )
    (net (code "83") (name "P2") (class "Default")
      (node (ref "IC2") (pin "6") (pinfunction "P2_6") (pintype "bidirectional"))
      (node (ref "R21") (pin "1") (pinfunction "1_1") (pintype "passive"))
      (node (ref "X5") (pin "4") (pinfunction "S_4") (pintype "passive"))
    )
    (net (code "84") (name "P3") (class "Default")
      (node (ref "IC2") (pin "7") (pinfunction "P3_7") (pintype "bidirectional"))
      (node (ref "R22") (pin "1") (pinfunction "1_1") (pintype "passive"))
      (node (ref "X6") (pin "4") (pinfunction "S_4") (pintype "passive"))
    )
    (net (code "85") (name "P4") (class "Default")
      (node (ref "IC2") (pin "9") (pinfunction "P4_9") (pintype "bidirectional"))
      (node (ref "R23") (pin "1") (pinfunction "1_1") (pintype "passive"))
      (node (ref "X7") (pin "4") (pinfunction "S_4") (pintype "passive"))
    )
    (net (code "86") (name "P5") (class "Default")
      (node (ref "IC2") (pin "10") (pinfunction "P5_10") (pintype "bidirectional"))
      (node (ref "R24") (pin "1") (pinfunction "1_1") (pintype "passive"))
      (node (ref "X8") (pin "4") (pinfunction "S_4") (pintype "passive"))
    )
    (net (code "87") (name "P6") (class "Default")
      (node (ref "IC2") (pin "11") (pinfunction "P6_11") (pintype "bidirectional"))
      (node (ref "R25") (pin "1") (pinfunction "1_1") (pintype "passive"))
      (node (ref "X9") (pin "4") (pinfunction "S_4") (pintype "passive"))
    )
    (net (code "88") (name "P7") (class "Default")
      (node (ref "IC2") (pin "12") (pinfunction "P7_12") (pintype "bidirectional"))
      (node (ref "R26") (pin "1") (pinfunction "1_1") (pintype "passive"))
      (node (ref "X10") (pin "4") (pinfunction "S_4") (pintype "passive"))
    )
    (net (code "89") (name "P8") (class "Default")
      (node (ref "IC4") (pin "4") (pinfunction "P0_4") (pintype "bidirectional"))
      (node (ref "R27") (pin "1") (pinfunction "1_1") (pintype "passive"))
      (node (ref "X12") (pin "4") (pinfunction "S_4") (pintype "passive"))
    )
    (net (code "90") (name "P9") (class "Default")
      (node (ref "IC4") (pin "5") (pinfunction "P1_5") (pintype "bidirectional"))
      (node (ref "R28") (pin "1") (pinfunction "1_1") (pintype "passive"))
      (node (ref "X13") (pin "4") (pinfunction "S_4") (pintype "passive"))
    )
    (net (code "91") (name "P10") (class "Default")
      (node (ref "IC4") (pin "6") (pinfunction "P2_6") (pintype "bidirectional"))
      (node (ref "R29") (pin "1") (pinfunction "1_1") (pintype "passive"))
      (node (ref "X14") (pin "4") (pinfunction "S_4") (pintype "passive"))
    )
    (net (code "92") (name "P11") (class "Default")
      (node (ref "IC4") (pin "7") (pinfunction "P3_7") (pintype "bidirectional"))
      (node (ref "R30") (pin "1") (pinfunction "1_1") (pintype "passive"))
      (node (ref "X15") (pin "4") (pinfunction "S_4") (pintype "passive"))
    )
    (net (code "93") (name "P12") (class "Default")
      (node (ref "IC4") (pin "9") (pinfunction "P4_9") (pintype "bidirectional"))
      (node (ref "R31") (pin "1") (pinfunction "1_1") (pintype "passive"))
      (node (ref "X16") (pin "4") (pinfunction "S_4") (pintype "passive"))
    )
    (net (code "94") (name "P13") (class "Default")
      (node (ref "IC4") (pin "10") (pinfunction "P5_10") (pintype "bidirectional"))
      (node (ref "R32") (pin "1") (pinfunction "1_1") (pintype "passive"))
      (node (ref "X17") (pin "4") (pinfunction "S_4") (pintype "passive"))
    )
    (net (code "95") (name "P14") (class "Default")
      (node (ref "IC4") (pin "11") (pinfunction "P6_11") (pintype "bidirectional"))
      (node (ref "R33") (pin "1") (pinfunction "1_1") (pintype "passive"))
      (node (ref "X18") (pin "4") (pinfunction "S_4") (pintype "passive"))
    )
    (net (code "96") (name "P15") (class "Default")
      (node (ref "IC4") (pin "12") (pinfunction "P7_12") (pintype "bidirectional"))
      (node (ref "R34") (pin "1") (pinfunction "1_1") (pintype "passive"))
      (node (ref "X19") (pin "4") (pinfunction "S_4") (pintype "passive"))
    )
    (net (code "97") (name "RST") (class "Default")
      (node (ref "JP1") (pin "5") (pinfunction "5_5") (pintype "passive"))
      (node (ref "U$20") (pin "RST") (pinfunction "RST_RST") (pintype "bidirectional"))
    )
    (net (code "98") (name "S8") (class "Default")
      (node (ref "IC3") (pin "4") (pinfunction "P0_4") (pintype "bidirectional"))
      (node (ref "R1") (pin "1") (pinfunction "1_1") (pintype "passive"))
    )
    (net (code "99") (name "S9") (class "Default")
      (node (ref "IC3") (pin "5") (pinfunction "P1_5") (pintype "bidirectional"))
      (node (ref "R10") (pin "2") (pinfunction "2_2") (pintype "passive"))
    )
    (net (code "100") (name "S10") (class "Default")
      (node (ref "IC3") (pin "6") (pinfunction "P2_6") (pintype "bidirectional"))
      (node (ref "R11") (pin "2") (pinfunction "2_2") (pintype "passive"))
    )
    (net (code "101") (name "S11") (class "Default")
      (node (ref "IC3") (pin "7") (pinfunction "P3_7") (pintype "bidirectional"))
      (node (ref "R12") (pin "2") (pinfunction "2_2") (pintype "passive"))
    )
    (net (code "102") (name "S12") (class "Default")
      (node (ref "IC3") (pin "9") (pinfunction "P4_9") (pintype "bidirectional"))
      (node (ref "R13") (pin "2") (pinfunction "2_2") (pintype "passive"))
    )
    (net (code "103") (name "S13") (class "Default")
      (node (ref "IC3") (pin "10") (pinfunction "P5_10") (pintype "bidirectional"))
      (node (ref "R14") (pin "2") (pinfunction "2_2") (pintype "passive"))
    )
    (net (code "104") (name "S14") (class "Default")
      (node (ref "IC3") (pin "11") (pinfunction "P6_11") (pintype "bidirectional"))
      (node (ref "R15") (pin "2") (pinfunction "2_2") (pintype "passive"))
    )
    (net (code "105") (name "S15") (class "Default")
      (node (ref "IC3") (pin "12") (pinfunction "P7_12") (pintype "bidirectional"))
      (node (ref "R16") (pin "2") (pinfunction "2_2") (pintype "passive"))
    )
    (net (code "106") (name "V24") (class "Default")
      (node (ref "C4") (pin "+") (pinfunction "+_+") (pintype "passive"))
      (node (ref "C8") (pin "1") (pinfunction "1_1") (pintype "passive"))
      (node (ref "R35") (pin "2") (pinfunction "2_2") (pintype "passive"))
      (node (ref "R36") (pin "2") (pinfunction "2_2") (pintype "passive"))
      (node (ref "R37") (pin "2") (pinfunction "2_2") (pintype "passive"))
      (node (ref "R38") (pin "2") (pinfunction "2_2") (pintype "passive"))
      (node (ref "R39") (pin "2") (pinfunction "2_2") (pintype "passive"))
      (node (ref "R40") (pin "2") (pinfunction "2_2") (pintype "passive"))
      (node (ref "R41") (pin "2") (pinfunction "2_2") (pintype "passive"))
      (node (ref "R42") (pin "2") (pinfunction "2_2") (pintype "passive"))
      (node (ref "R43") (pin "2") (pinfunction "2_2") (pintype "passive"))
      (node (ref "R44") (pin "2") (pinfunction "2_2") (pintype "passive"))
      (node (ref "R45") (pin "2") (pinfunction "2_2") (pintype "passive"))
      (node (ref "R46") (pin "2") (pinfunction "2_2") (pintype "passive"))
      (node (ref "R47") (pin "2") (pinfunction "2_2") (pintype "passive"))
      (node (ref "R48") (pin "2") (pinfunction "2_2") (pintype "passive"))
      (node (ref "R49") (pin "2") (pinfunction "2_2") (pintype "passive"))
      (node (ref "R50") (pin "2") (pinfunction "2_2") (pintype "passive"))
      (node (ref "U$1") (pin "P2") (pinfunction "S_P2") (pintype "passive"))
      (node (ref "U$12") (pin "P2") (pinfunction "S_P2") (pintype "passive"))
      (node (ref "U$13") (pin "P2") (pinfunction "S_P2") (pintype "passive"))
      (node (ref "U$14") (pin "P2") (pinfunction "S_P2") (pintype "passive"))
      (node (ref "U$15") (pin "P2") (pinfunction "S_P2") (pintype "passive"))
      (node (ref "U$16") (pin "P2") (pinfunction "S_P2") (pintype "passive"))
      (node (ref "U$17") (pin "P2") (pinfunction "S_P2") (pintype "passive"))
      (node (ref "U$18") (pin "P2") (pinfunction "S_P2") (pintype "passive"))
      (node (ref "U$19") (pin "P2") (pinfunction "S_P2") (pintype "passive"))
      (node (ref "U$2") (pin "P2") (pinfunction "S_P2") (pintype "passive"))
      (node (ref "U$3") (pin "P2") (pinfunction "S_P2") (pintype "passive"))
      (node (ref "U$4") (pin "P2") (pinfunction "S_P2") (pintype "passive"))
      (node (ref "U$5") (pin "P2") (pinfunction "S_P2") (pintype "passive"))
      (node (ref "U$6") (pin "P2") (pinfunction "S_P2") (pintype "passive"))
      (node (ref "U$7") (pin "P2") (pinfunction "S_P2") (pintype "passive"))
      (node (ref "U$8") (pin "P2") (pinfunction "S_P2") (pintype "passive"))
      (node (ref "X1") (pin "1") (pinfunction "S_1") (pintype "passive"))
      (node (ref "X22") (pin "1") (pinfunction "S_1") (pintype "passive"))
    )
    (net (code "107") (name "VCC") (class "Default")
      (node (ref "C3") (pin "1") (pinfunction "1_1") (pintype "passive"))
      (node (ref "C6") (pin "1") (pinfunction "1_1") (pintype "passive"))
      (node (ref "C7") (pin "+") (pinfunction "+_+") (pintype "passive"))
      (node (ref "IC1") (pin "16") (pinfunction "VDD_16") (pintype "power_in"))
      (node (ref "IC2") (pin "1") (pinfunction "A0_1") (pintype "input"))
      (node (ref "IC2") (pin "16") (pinfunction "VDD_16") (pintype "power_in"))
      (node (ref "IC3") (pin "16") (pinfunction "VDD_16") (pintype "power_in"))
      (node (ref "IC3") (pin "2") (pinfunction "A1_2") (pintype "input"))
      (node (ref "IC4") (pin "16") (pinfunction "VDD_16") (pintype "power_in"))
      (node (ref "IC4") (pin "3") (pinfunction "A2_3") (pintype "input"))
      (node (ref "JP1") (pin "2") (pinfunction "2_2") (pintype "passive"))
      (node (ref "R17") (pin "2") (pinfunction "2_2") (pintype "passive"))
      (node (ref "R18") (pin "2") (pinfunction "2_2") (pintype "passive"))
      (node (ref "R19") (pin "2") (pinfunction "2_2") (pintype "passive"))
      (node (ref "R20") (pin "2") (pinfunction "2_2") (pintype "passive"))
      (node (ref "R21") (pin "2") (pinfunction "2_2") (pintype "passive"))
      (node (ref "R22") (pin "2") (pinfunction "2_2") (pintype "passive"))
      (node (ref "R23") (pin "2") (pinfunction "2_2") (pintype "passive"))
      (node (ref "R24") (pin "2") (pinfunction "2_2") (pintype "passive"))
      (node (ref "R25") (pin "2") (pinfunction "2_2") (pintype "passive"))
      (node (ref "R26") (pin "2") (pinfunction "2_2") (pintype "passive"))
      (node (ref "R27") (pin "2") (pinfunction "2_2") (pintype "passive"))
      (node (ref "R28") (pin "2") (pinfunction "2_2") (pintype "passive"))
      (node (ref "R29") (pin "2") (pinfunction "2_2") (pintype "passive"))
      (node (ref "R30") (pin "2") (pinfunction "2_2") (pintype "passive"))
      (node (ref "R31") (pin "2") (pinfunction "2_2") (pintype "passive"))
      (node (ref "R32") (pin "2") (pinfunction "2_2") (pintype "passive"))
      (node (ref "R33") (pin "2") (pinfunction "2_2") (pintype "passive"))
      (node (ref "R34") (pin "2") (pinfunction "2_2") (pintype "passive"))
      (node (ref "U$10") (pin "VCC") (pinfunction "VCC_VCC") (pintype "passive"))
      (node (ref "U$20") (pin "VCC") (pinfunction "VCC_VCC") (pintype "bidirectional"))
      (node (ref "X11") (pin "1") (pinfunction "S_1") (pintype "passive"))
      (node (ref "X21") (pin "1") (pinfunction "S_1") (pintype "passive"))
    )
    (net (code "108") (name "unconnected-(IC1-~{INT}-Pad13)") (class "Default")
      (node (ref "IC1") (pin "13") (pinfunction "~{INT}_13") (pintype "output"))
    )
    (net (code "109") (name "unconnected-(IC2-~{INT}-Pad13)") (class "Default")
      (node (ref "IC2") (pin "13") (pinfunction "~{INT}_13") (pintype "output"))
    )
    (net (code "110") (name "unconnected-(IC3-~{INT}-Pad13)") (class "Default")
      (node (ref "IC3") (pin "13") (pinfunction "~{INT}_13") (pintype "output"))
    )
    (net (code "111") (name "unconnected-(IC4-~{INT}-Pad13)") (class "Default")
      (node (ref "IC4") (pin "13") (pinfunction "~{INT}_13") (pintype "output"))
    )
    (net (code "112") (name "unconnected-(U$20-GND3-PadGND2)") (class "Default")
      (node (ref "U$20") (pin "GND2") (pinfunction "GND3_GND2") (pintype "bidirectional"))
    )
    (net (code "113") (name "unconnected-(U$20-GND4-PadGND3)") (class "Default")
      (node (ref "U$20") (pin "GND3") (pinfunction "GND4_GND3") (pintype "bidirectional"))
    )
    (net (code "114") (name "unconnected-(U$20-PadD10)") (class "Default")
      (node (ref "U$20") (pin "D10") (pinfunction "D10_D10") (pintype "bidirectional"))
    )
    (net (code "115") (name "unconnected-(U$20-PadDTR)") (class "Default")
      (node (ref "U$20") (pin "DTR") (pinfunction "DTR_DTR") (pintype "bidirectional"))
    )
    (net (code "116") (name "unconnected-(U$20-PadRAW)") (class "Default")
      (node (ref "U$20") (pin "RAW") (pinfunction "RAW_RAW") (pintype "bidirectional"))
    )
    (net (code "117") (name "unconnected-(U$20-PadRST1)") (class "Default")
      (node (ref "U$20") (pin "RST1") (pinfunction "RST1_RST1") (pintype "bidirectional"))
    )
    (net (code "118") (name "unconnected-(U$20-PadRX1-1)") (class "Default")
      (node (ref "U$20") (pin "RX1-1") (pinfunction "RX1-1_RX1-1") (pintype "bidirectional"))
    )
    (net (code "119") (name "unconnected-(U$20-PadTX0-1)") (class "Default")
      (node (ref "U$20") (pin "TX0-1") (pinfunction "TX0-1_TX0-1") (pintype "bidirectional"))
    )
    (net (code "120") (name "unconnected-(U$20-PadVCC1)") (class "Default")
      (node (ref "U$20") (pin "VCC1") (pinfunction "VCC1_VCC1") (pintype "bidirectional"))
    )
  )
)
